# EG8010.net
KiCad netlist of a schematic drawn in Altium Designer
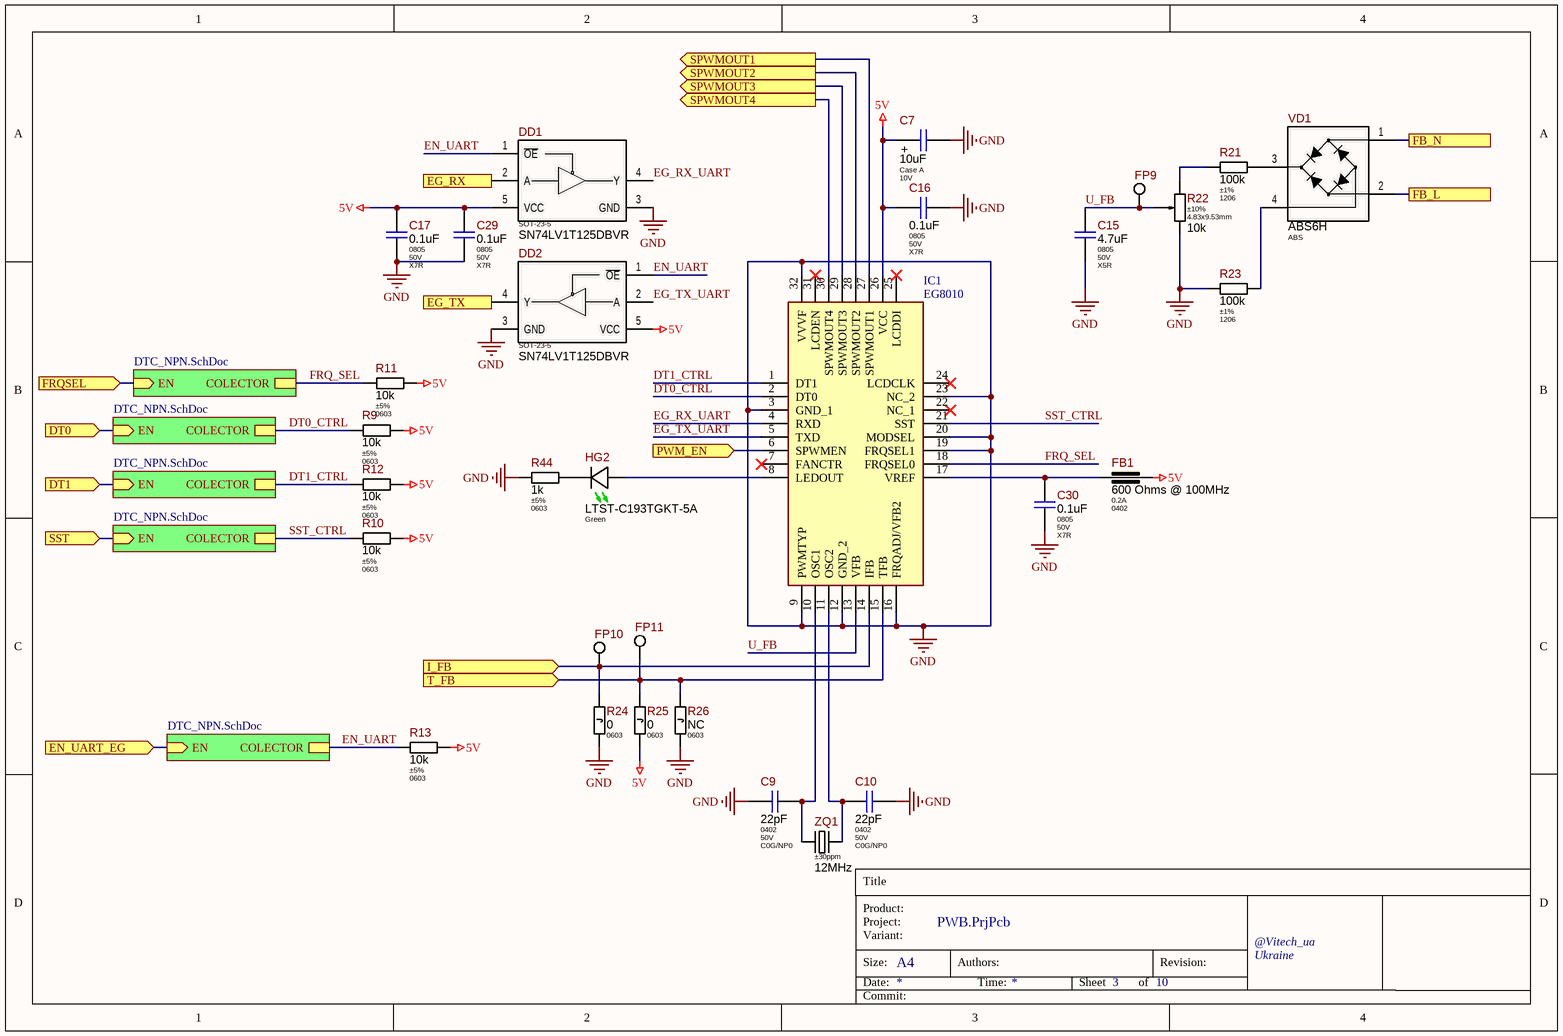
[diagram p0: EG8010.SchDoc]

(export (version "E")
  (design (tool "Eeschema 10.0.6"))
  (components
    (comp (ref "C7")
      (value "10uF")
      (footprint "C_TANTAL_CASE_A_MED")
      (description "10uF 10V ±10% Case A Tantalum Capacitor RoHS, 3.4Ohm")
      (fields
        (field (name "PACKAGE") "Case A")
        (field (name "VOLTAGE") "10V")
        (field (name "PART NUMBER") "293D106X9010A2TE3")
        (field (name "MANUFACTURER") "Vishay")
      )
      (libsource (lib "capacitors") (part "293D106X9010A2TE3"))
    )
    (comp (ref "C9")
      (value "22pF")
      (footprint "C_CERAMIC_0402_MED")
      (description "22pF 50V NP0, C0G ±5% 0402 Ceramic Capacitor RoHS")
      (fields
        (field (name "PACKAGE") "0402")
        (field (name "VOLTAGE") "50V")
        (field (name "DIELECTRIC TYPE") "C0G/NP0")
        (field (name "PART NUMBER") "CL05C220JB5NNNC")
        (field (name "MANUFACTURER") "Samsung Electro-Mechanics")
      )
      (libsource (lib "capacitors") (part "CL05C220JB5NNNC"))
    )
    (comp (ref "C10")
      (value "22pF")
      (footprint "C_CERAMIC_0402_MED")
      (description "22pF 50V NP0, C0G ±5% 0402 Ceramic Capacitor RoHS")
      (fields
        (field (name "PACKAGE") "0402")
        (field (name "VOLTAGE") "50V")
        (field (name "DIELECTRIC TYPE") "C0G/NP0")
        (field (name "PART NUMBER") "CL05C220JB5NNNC")
        (field (name "MANUFACTURER") "Samsung Electro-Mechanics")
      )
      (libsource (lib "capacitors") (part "CL05C220JB5NNNC"))
    )
    (comp (ref "C15")
      (value "4.7uF")
      (footprint "C_CERAMIC_0805_MED")
      (description "4.7uF 50V X5R ±10% 0805 Ceramic Capacitor RoHS")
      (fields
        (field (name "PACKAGE") "0805")
        (field (name "VOLTAGE") "50V")
        (field (name "DIELECTRIC TYPE") "X5R")
        (field (name "PART NUMBER") "GRM21BR61H475KE51L")
        (field (name "MANUFACTURER") "Murata Electronics")
      )
      (libsource (lib "capacitors") (part "GRM21BR61H475KE51L"))
    )
    (comp (ref "C16")
      (value "0.1uF")
      (footprint "CAP-0805(2012)X85T10")
      (description "100nF 50V X7R ±10% 0805 Ceramic Capacitor RoHS")
      (fields
        (field (name "PACKAGE") "0805")
        (field (name "VOLTAGE") "50V")
        (field (name "DIELECTRIC TYPE") "X7R")
        (field (name "PART NUMBER") "CL21B104KBCNNNC")
        (field (name "MANUFACTURER") "Samsung Electro-Mechanics")
      )
      (libsource (lib "capacitors") (part "CL21B104KBCNNNC"))
    )
    (comp (ref "C17")
      (value "0.1uF")
      (footprint "CAP-0805(2012)X85T10")
      (description "100nF 50V X7R ±10% 0805 Ceramic Capacitor RoHS")
      (fields
        (field (name "PACKAGE") "0805")
        (field (name "VOLTAGE") "50V")
        (field (name "DIELECTRIC TYPE") "X7R")
        (field (name "PART NUMBER") "CL21B104KBCNNNC")
        (field (name "MANUFACTURER") "Samsung Electro-Mechanics")
      )
      (libsource (lib "capacitors") (part "CL21B104KBCNNNC"))
    )
    (comp (ref "C29")
      (value "0.1uF")
      (footprint "CAP-0805(2012)X85T10")
      (description "100nF 50V X7R ±10% 0805 Ceramic Capacitor RoHS")
      (fields
        (field (name "PACKAGE") "0805")
        (field (name "VOLTAGE") "50V")
        (field (name "DIELECTRIC TYPE") "X7R")
        (field (name "PART NUMBER") "CL21B104KBCNNNC")
        (field (name "MANUFACTURER") "Samsung Electro-Mechanics")
      )
      (libsource (lib "capacitors") (part "CL21B104KBCNNNC"))
    )
    (comp (ref "C30")
      (value "0.1uF")
      (footprint "CAP-0805(2012)X85T10")
      (description "100nF 50V X7R ±10% 0805 Ceramic Capacitor RoHS")
      (fields
        (field (name "PACKAGE") "0805")
        (field (name "VOLTAGE") "50V")
        (field (name "DIELECTRIC TYPE") "X7R")
        (field (name "PART NUMBER") "CL21B104KBCNNNC")
        (field (name "MANUFACTURER") "Samsung Electro-Mechanics")
      )
      (libsource (lib "capacitors") (part "CL21B104KBCNNNC"))
    )
    (comp (ref "DD1")
      (value "SN74LV1T125DBVR")
      (footprint "SOT-23-5")
      (description "Single Power Supply Single Buffer Gate with 3-State Output CMOS Logic Level Shifter, SOT-23-5")
      (fields
        (field (name "PACKAGE") "SOT-23-5")
        (field (name "PART NUMBER") "SN74LV1T125DBVR")
        (field (name "MANUFACTURER") "Texas Instruments")
      )
      (libsource (lib "ic") (part "SN74LV1T125DBVR"))
    )
    (comp (ref "DD2")
      (value "SN74LV1T125DBVR")
      (footprint "SOT-23-5")
      (description "Single Power Supply Single Buffer Gate with 3-State Output CMOS Logic Level Shifter, SOT-23-5")
      (fields
        (field (name "PACKAGE") "SOT-23-5")
        (field (name "PART NUMBER") "SN74LV1T125DBVR")
        (field (name "MANUFACTURER") "Texas Instruments")
      )
      (libsource (lib "") (part "SN74LV1T125DBVR_1"))
    )
    (comp (ref "FB1")
      (value "600 Ohms @ 100MHz")
      (footprint "BLM15xxxxxSN1x_MED")
      (description "600 Ohms @ 100MHz Power Line Ferrite Bead 0402, 200mA 650mOhm")
      (fields
        (field (name "CURRENT") "0.2A")
        (field (name "PACKAGE") "0402")
        (field (name "PART NUMBER") "BLM15BD601SN1D")
        (field (name "TOLERANCE") "±25%")
      )
      (libsource (lib "inductors") (part "BLM15BD601SN1D"))
    )
    (comp (ref "FP9")
      (value "PAD-1.75mm")
      (footprint "PAD-1.75mm")
      (description "1.75mm Pad for Plug-In or Receptacle")
      (fields (field (name "MANUFACTURER") "NONE"))
      (libsource (lib "probetools") (part "PAD-1.75mm"))
    )
    (comp (ref "FP10")
      (value "PAD-1.75mm")
      (footprint "PAD-1.75mm")
      (description "1.75mm Pad for Plug-In or Receptacle")
      (fields (field (name "MANUFACTURER") "NONE"))
      (libsource (lib "probetools") (part "PAD-1.75mm"))
    )
    (comp (ref "FP11")
      (value "PAD-1.75mm")
      (footprint "PAD-1.75mm")
      (description "1.75mm Pad for Plug-In or Receptacle")
      (fields (field (name "MANUFACTURER") "NONE"))
      (libsource (lib "probetools") (part "PAD-1.75mm"))
    )
    (comp (ref "HG2")
      (value "LTST-C193TGKT-5A")
      (footprint "LTST-C193xGKT-5A")
      (description "Indication LED, Green 525nm, Clear, SMD 0603, Vf 2.5V - 3.1V, 28 ~ 280mcd @ 5 mA, 130°")
      (fields
        (field (name "PART NUMBER") "LTST-C193TGKT-5A")
        (field (name "COLOR") "Green")
        (field (name "MANUFACTURER") "Lite-On Optoelectronics")
      )
      (libsource (lib "opto") (part "LTST-C193TGKT-5A"))
    )
    (comp (ref "IC1")
      (value "EG8010")
      (footprint "vitech_lib:QFP80P900X900X160-32N")
      (description "Integrated Circuit")
      (libsource (lib "*") (part "EG8010"))
    )
    (comp (ref "R9")
      (value "10k")
      (footprint "R_ANY_CHIP_0603_MED")
      (description "10 kOhms ±5%, 1/10W 0603 Thick Film Resistor")
      (fields
        (field (name "TOLERANCE") "±5%")
        (field (name "PACKAGE") "0603")
        (field (name "PART NUMBER") "RC0603JR-0710KL")
        (field (name "MANUFACTURER") "Yageo")
      )
      (libsource (lib "resistors") (part "RC0603JR-0710KL"))
    )
    (comp (ref "R10")
      (value "10k")
      (footprint "R_ANY_CHIP_0603_MED")
      (description "10 kOhms ±5%, 1/10W 0603 Thick Film Resistor")
      (fields
        (field (name "TOLERANCE") "±5%")
        (field (name "PACKAGE") "0603")
        (field (name "PART NUMBER") "RC0603JR-0710KL")
        (field (name "MANUFACTURER") "Yageo")
      )
      (libsource (lib "resistors") (part "RC0603JR-0710KL"))
    )
    (comp (ref "R11")
      (value "10k")
      (footprint "R_ANY_CHIP_0603_MED")
      (description "10 kOhms ±5%, 1/10W 0603 Thick Film Resistor")
      (fields
        (field (name "TOLERANCE") "±5%")
        (field (name "PACKAGE") "0603")
        (field (name "PART NUMBER") "RC0603JR-0710KL")
        (field (name "MANUFACTURER") "Yageo")
      )
      (libsource (lib "resistors") (part "RC0603JR-0710KL"))
    )
    (comp (ref "R12")
      (value "10k")
      (footprint "R_ANY_CHIP_0603_MED")
      (description "10 kOhms ±5%, 1/10W 0603 Thick Film Resistor")
      (fields
        (field (name "TOLERANCE") "±5%")
        (field (name "PACKAGE") "0603")
        (field (name "PART NUMBER") "RC0603JR-0710KL")
        (field (name "MANUFACTURER") "Yageo")
      )
      (libsource (lib "resistors") (part "RC0603JR-0710KL"))
    )
    (comp (ref "R13")
      (value "10k")
      (footprint "R_ANY_CHIP_0603_MED")
      (description "10 kOhms ±5%, 1/10W 0603 Thick Film Resistor")
      (fields
        (field (name "TOLERANCE") "±5%")
        (field (name "PACKAGE") "0603")
        (field (name "PART NUMBER") "RC0603JR-0710KL")
        (field (name "MANUFACTURER") "Yageo")
      )
      (libsource (lib "resistors") (part "RC0603JR-0710KL"))
    )
    (comp (ref "R21")
      (value "100k")
      (footprint "R_ANY_CHIP_1206_MED")
      (description "100 kOhms ±1%, 1/4W 1206 Thick Film Resistor")
      (fields
        (field (name "TOLERANCE") "±1%")
        (field (name "PACKAGE") "1206")
        (field (name "PART NUMBER") "RC1206FR-07100KL")
        (field (name "MANUFACTURER") "Yageo")
      )
      (libsource (lib "resistors") (part "RC1206FR-07100KL"))
    )
    (comp (ref "R22")
      (value "10k")
      (footprint "3296W-1-xxx")
      (description "10 kOhms ±10% Trimmer Resistor, 0.5W, Through Hole 3/8\", 4.83x9.53mm, 10.03mm Height")
      (fields
        (field (name "TOLERANCE") "±10%")
        (field (name "PACKAGE") "4.83x9.53mm")
        (field (name "PART NUMBER") "3296W-1-103LF")
        (field (name "MANUFACTURER") "Bourns")
      )
      (libsource (lib "resistors") (part "3296W-1-103LF"))
    )
    (comp (ref "R23")
      (value "100k")
      (footprint "R_ANY_CHIP_1206_MED")
      (description "100 kOhms ±1%, 1/4W 1206 Thick Film Resistor")
      (fields
        (field (name "TOLERANCE") "±1%")
        (field (name "PACKAGE") "1206")
        (field (name "PART NUMBER") "RC1206FR-07100KL")
        (field (name "MANUFACTURER") "Yageo")
      )
      (libsource (lib "resistors") (part "RC1206FR-07100KL"))
    )
    (comp (ref "R24")
      (value "0")
      (footprint "R_ANY_CHIP_0603_MED")
      (description "0 Ohms Jumper, 1/10W 0603 Thick Film Resistor")
      (fields
        (field (name "TOLERANCE") "±5%")
        (field (name "PACKAGE") "0603")
        (field (name "PART NUMBER") "RC0603JR-070RL")
      )
      (libsource (lib "resistors") (part "RC0603JR-070RL"))
    )
    (comp (ref "R25")
      (value "0")
      (footprint "R_ANY_CHIP_0603_MED")
      (description "0 Ohms Jumper, 1/10W 0603 Thick Film Resistor")
      (fields
        (field (name "TOLERANCE") "±5%")
        (field (name "PACKAGE") "0603")
        (field (name "PART NUMBER") "RC0603JR-070RL")
      )
      (libsource (lib "resistors") (part "RC0603JR-070RL"))
    )
    (comp (ref "R26")
      (value "NC")
      (footprint "R_ANY_CHIP_0603_MED")
      (description "0 Ohms Jumper, 1/10W 0603 Thick Film Resistor")
      (fields
        (field (name "TOLERANCE") "±5%")
        (field (name "PACKAGE") "0603")
        (field (name "PART NUMBER") "RC0603JR-070RL")
      )
      (libsource (lib "resistors") (part "RC0603JR-070RL"))
    )
    (comp (ref "R44")
      (value "1k")
      (footprint "R_ANY_CHIP_0603_MED")
      (description "1 kOhms ±5%, 1/10W 0603 Thick Film Resistor")
      (fields
        (field (name "TOLERANCE") "±5%")
        (field (name "PACKAGE") "0603")
        (field (name "PART NUMBER") "RC0603JR-071KL")
        (field (name "MANUFACTURER") "Yageo")
      )
      (libsource (lib "resistors") (part "RC0603JR-071KL"))
    )
    (comp (ref "VD1")
      (value "ABS6H")
      (footprint "ABSxx-Series")
      (description "1A, 600V Standard Bridge Rectifier, ABS Package")
      (fields
        (field (name "PART NUMBER") "ABS6H")
        (field (name "PACKAGE") "ABS")
        (field (name "MANUFACTURER") "Taiwan Semiconductor")
        (field (name "VOLTAGE") "600V")
      )
      (libsource (lib "diodes") (part "ABS6H"))
    )
    (comp (ref "ZQ1")
      (value "CSM4Z-A2B3C3-40-12.0D18")
      (footprint "CSM4-Series")
      (description "12MHz, 18pF, ±30ppm, 40Ohm ESR, 1mW DL Crystal Quartz")
      (fields
        (field (name "FREQUENCY TOLERANCE") "±30ppm")
        (field (name "FREQUENCY") "12MHz")
        (field (name "MANUFACTURER") "Cardinal Components Inc.")
      )
      (libsource (lib "oscillators") (part "CSM4Z-A2B3C3-40-12.0D18"))
    )
  )
  (nets
    (net (code "2") (name "/DT0_CTRL") (class "Default")
      (node (ref "IC1") (pin "2") (pinfunction "DT0_2") (pintype "passive"))
      (node (ref "R9") (pin "1") (pintype "passive"))
    )
    (net (code "4") (name "/DT1_CTRL") (class "Default")
      (node (ref "IC1") (pin "1") (pinfunction "DT1_1") (pintype "passive"))
      (node (ref "R12") (pin "1") (pintype "passive"))
    )
    (net (code "5") (name "/EG_RX") (class "Default")
      (node (ref "DD1") (pin "2") (pinfunction "A_2") (pintype "passive"))
    )
    (net (code "6") (name "/EG_RX_UART") (class "Default")
      (node (ref "DD1") (pin "4") (pinfunction "Y_4") (pintype "passive"))
      (node (ref "IC1") (pin "4") (pinfunction "RXD_4") (pintype "passive"))
    )
    (net (code "7") (name "/EG_TX") (class "Default")
      (node (ref "DD2") (pin "4") (pinfunction "Y_4") (pintype "passive"))
    )
    (net (code "8") (name "/EG_TX_UART") (class "Default")
      (node (ref "DD2") (pin "2") (pinfunction "A_2") (pintype "passive"))
      (node (ref "IC1") (pin "5") (pinfunction "TXD_5") (pintype "passive"))
    )
    (net (code "9") (name "/EN_UART") (class "Default")
      (node (ref "DD1") (pin "1") (pinfunction "~{OE}_1") (pintype "passive"))
      (node (ref "DD2") (pin "1") (pinfunction "~{OE}_1") (pintype "passive"))
      (node (ref "R13") (pin "1") (pintype "passive"))
    )
    (net (code "11") (name "/FB_L") (class "Default")
      (node (ref "VD1") (pin "2") (pinfunction "~_2") (pintype "passive"))
    )
    (net (code "12") (name "/FB_N") (class "Default")
      (node (ref "VD1") (pin "1") (pinfunction "~_1") (pintype "passive"))
    )
    (net (code "14") (name "/FRQ_SEL") (class "Default")
      (node (ref "IC1") (pin "18") (pinfunction "FRQSEL0_18") (pintype "passive"))
      (node (ref "R11") (pin "1") (pintype "passive"))
    )
    (net (code "15") (name "/I_FB") (class "Default")
      (node (ref "FP10") (pin "1") (pintype "passive"))
      (node (ref "IC1") (pin "14") (pinfunction "IFB_14") (pintype "passive"))
      (node (ref "R24") (pin "1") (pintype "passive"))
    )
    (net (code "16") (name "/PWM_EN") (class "Default")
      (node (ref "IC1") (pin "6") (pinfunction "SPWMEN_6") (pintype "passive"))
    )
    (net (code "17") (name "/SPWMOUT1") (class "Default")
      (node (ref "IC1") (pin "27") (pinfunction "SPWMOUT1_27") (pintype "passive"))
    )
    (net (code "18") (name "/SPWMOUT2") (class "Default")
      (node (ref "IC1") (pin "28") (pinfunction "SPWMOUT2_28") (pintype "passive"))
    )
    (net (code "19") (name "/SPWMOUT3") (class "Default")
      (node (ref "IC1") (pin "29") (pinfunction "SPWMOUT3_29") (pintype "passive"))
    )
    (net (code "20") (name "/SPWMOUT4") (class "Default")
      (node (ref "IC1") (pin "30") (pinfunction "SPWMOUT4_30") (pintype "passive"))
    )
    (net (code "22") (name "/SST_CTRL") (class "Default")
      (node (ref "IC1") (pin "21") (pinfunction "SST_21") (pintype "passive"))
      (node (ref "R10") (pin "1") (pintype "passive"))
    )
    (net (code "23") (name "/T_FB") (class "Default")
      (node (ref "FP11") (pin "1") (pintype "passive"))
      (node (ref "IC1") (pin "15") (pinfunction "TFB_15") (pintype "passive"))
      (node (ref "R25") (pin "1") (pintype "passive"))
      (node (ref "R26") (pin "1") (pintype "passive"))
    )
    (net (code "24") (name "/U_FB") (class "Default")
      (node (ref "C15") (pin "1") (pinfunction "1_1") (pintype "passive"))
      (node (ref "FP9") (pin "1") (pintype "passive"))
      (node (ref "IC1") (pin "13") (pinfunction "VFB_13") (pintype "passive"))
      (node (ref "R22") (pin "2") (pinfunction "WIPER_2") (pintype "passive"))
    )
    (net (code "25") (name "5V") (class "Default")
      (node (ref "C16") (pin "1") (pinfunction "1_1") (pintype "passive"))
      (node (ref "C17") (pin "1") (pinfunction "1_1") (pintype "passive"))
      (node (ref "C29") (pin "1") (pinfunction "1_1") (pintype "passive"))
      (node (ref "C7") (pin "1") (pinfunction "1_1") (pintype "passive"))
      (node (ref "DD1") (pin "5") (pinfunction "VCC_5") (pintype "passive"))
      (node (ref "DD2") (pin "5") (pinfunction "VCC_5") (pintype "passive"))
      (node (ref "FB1") (pin "1") (pintype "passive"))
      (node (ref "IC1") (pin "26") (pinfunction "VCC_26") (pintype "passive"))
      (node (ref "R10") (pin "2") (pintype "passive"))
      (node (ref "R11") (pin "2") (pintype "passive"))
      (node (ref "R12") (pin "2") (pintype "passive"))
      (node (ref "R13") (pin "2") (pintype "passive"))
      (node (ref "R25") (pin "2") (pintype "passive"))
      (node (ref "R9") (pin "2") (pintype "passive"))
    )
    (net (code "26") (name "GND") (class "Default")
      (node (ref "C10") (pin "2") (pinfunction "2_2") (pintype "passive"))
      (node (ref "C15") (pin "2") (pinfunction "2_2") (pintype "passive"))
      (node (ref "C16") (pin "2") (pinfunction "2_2") (pintype "passive"))
      (node (ref "C17") (pin "2") (pinfunction "2_2") (pintype "passive"))
      (node (ref "C29") (pin "2") (pinfunction "2_2") (pintype "passive"))
      (node (ref "C30") (pin "2") (pinfunction "2_2") (pintype "passive"))
      (node (ref "C7") (pin "2") (pinfunction "2_2") (pintype "passive"))
      (node (ref "C9") (pin "1") (pinfunction "1_1") (pintype "passive"))
      (node (ref "DD1") (pin "3") (pinfunction "GND_3") (pintype "passive"))
      (node (ref "DD2") (pin "3") (pinfunction "GND_3") (pintype "passive"))
      (node (ref "IC1") (pin "12") (pinfunction "GND_2_12") (pintype "passive"))
      (node (ref "IC1") (pin "16") (pinfunction "FRQADJ/VFB2_16") (pintype "passive"))
      (node (ref "IC1") (pin "19") (pinfunction "FRQSEL1_19") (pintype "passive"))
      (node (ref "IC1") (pin "20") (pinfunction "MODSEL_20") (pintype "passive"))
      (node (ref "IC1") (pin "23") (pinfunction "NC_2_23") (pintype "passive"))
      (node (ref "IC1") (pin "3") (pinfunction "GND_1_3") (pintype "passive"))
      (node (ref "IC1") (pin "32") (pinfunction "VVVF_32") (pintype "passive"))
      (node (ref "IC1") (pin "9") (pinfunction "PWMTYP_9") (pintype "passive"))
      (node (ref "R22") (pin "1") (pinfunction "CCW_1") (pintype "passive"))
      (node (ref "R23") (pin "1") (pintype "passive"))
      (node (ref "R24") (pin "2") (pintype "passive"))
      (node (ref "R26") (pin "2") (pintype "passive"))
      (node (ref "R44") (pin "1") (pintype "passive"))
    )
    (net (code "27") (name "Net-(HG2-Anode)") (class "Default")
      (node (ref "HG2") (pin "AN") (pinfunction "Anode_AN") (pintype "passive"))
      (node (ref "IC1") (pin "8") (pinfunction "LEDOUT_8") (pintype "passive"))
    )
    (net (code "28") (name "Net-(HG2-Cathode)") (class "Default")
      (node (ref "HG2") (pin "CA") (pinfunction "Cathode_CA") (pintype "passive"))
      (node (ref "R44") (pin "2") (pintype "passive"))
    )
    (net (code "29") (name "Net-(IC1-OSC1)") (class "Default")
      (node (ref "C9") (pin "2") (pinfunction "2_2") (pintype "passive"))
      (node (ref "IC1") (pin "10") (pinfunction "OSC1_10") (pintype "passive"))
      (node (ref "ZQ1") (pin "2") (pinfunction "XTAL2_2") (pintype "passive"))
    )
    (net (code "30") (name "Net-(IC1-OSC2)") (class "Default")
      (node (ref "C10") (pin "1") (pinfunction "1_1") (pintype "passive"))
      (node (ref "IC1") (pin "11") (pinfunction "OSC2_11") (pintype "passive"))
      (node (ref "ZQ1") (pin "1") (pinfunction "XTAL1_1") (pintype "passive"))
    )
    (net (code "31") (name "Net-(IC1-VREF)") (class "Default")
      (node (ref "C30") (pin "1") (pinfunction "1_1") (pintype "passive"))
      (node (ref "FB1") (pin "2") (pintype "passive"))
      (node (ref "IC1") (pin "17") (pinfunction "VREF_17") (pintype "passive"))
    )
    (net (code "32") (name "Net-(R22-CW)") (class "Default")
      (node (ref "R21") (pin "1") (pintype "passive"))
      (node (ref "R22") (pin "3") (pinfunction "CW_3") (pintype "passive"))
    )
    (net (code "33") (name "Net-(VD1-+)") (class "Default")
      (node (ref "R21") (pin "2") (pintype "passive"))
      (node (ref "VD1") (pin "3") (pinfunction "+_3") (pintype "passive"))
    )
    (net (code "34") (name "Net-(VD1--)") (class "Default")
      (node (ref "R23") (pin "2") (pintype "passive"))
      (node (ref "VD1") (pin "4") (pinfunction "-_4") (pintype "passive"))
    )
    (net (code "35") (name "unconnected-(IC1-FANCTR-Pad7)") (class "Default")
      (node (ref "IC1") (pin "7") (pinfunction "FANCTR_7") (pintype "passive+no_connect"))
    )
    (net (code "36") (name "unconnected-(IC1-LCDCLK-Pad24)") (class "Default")
      (node (ref "IC1") (pin "24") (pinfunction "LCDCLK_24") (pintype "passive+no_connect"))
    )
    (net (code "37") (name "unconnected-(IC1-LCDDI-Pad25)") (class "Default")
      (node (ref "IC1") (pin "25") (pinfunction "LCDDI_25") (pintype "passive+no_connect"))
    )
    (net (code "38") (name "unconnected-(IC1-LCDEN-Pad31)") (class "Default")
      (node (ref "IC1") (pin "31") (pinfunction "LCDEN_31") (pintype "passive+no_connect"))
    )
    (net (code "39") (name "unconnected-(IC1-NC_1-Pad22)") (class "Default")
      (node (ref "IC1") (pin "22") (pinfunction "NC_1_22") (pintype "passive+no_connect"))
    )
  )
)
